# MCU.net
KiCad netlist of a schematic drawn in Altium Designer
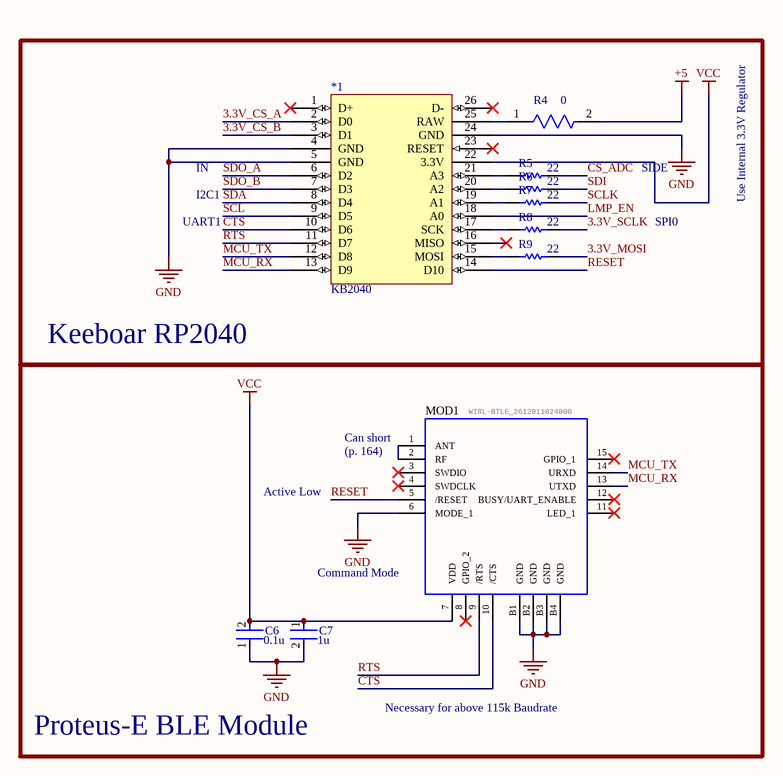
[diagram p0: MCU.SchDoc]

(export (version "E")
  (design (tool "Eeschema 10.0.6"))
  (components
    (comp (ref "*1")
      (value "KB2040")
      (footprint "CAC-254P3300X1775-26N")
      (description "Adafruit KB2040 - RP2040 Kee Boar Driver")
      (libsource (lib "UCLA") (part "KB2040-Symbol-1"))
    )
    (comp (ref "C6")
      (value "0.1u")
      (footprint "FP-GCJ188-0_2-IPC_C")
      (description "Cap Ceramic 0.1uF 50V X7R 10% Pad SMD 0603 Soft Termination +125°C Automotive T/R")
      (fields (field (name "TOLERANCE") "10%"))
      (libsource (lib "Altium Content Vault") (part "f23184f103b6ebe33a8c269c53dcba6"))
    )
    (comp (ref "C7")
      (value "1u")
      (footprint "FP-GCM188-0_1-IPC_B")
      (description "Ceramic Capacitor for Automotive 1uF  ±10% 16VDC X7R 0603 Paper T/R")
      (fields (field (name "VOLTAGE") "16V") (field (name "TOLERANCE") "10%"))
      (libsource (lib "Altium Content Vault") (part "02cd4be3c70576c341d710602a673aa"))
    )
    (comp (ref "MOD1")
      (value "WIRL-BTLE_2612011024000")
      (footprint "WE-FP-6")
      (description "Proteus-e Bluetooth® LE 5.1 Module")
      (fields (field (name "PART NUMBER") "2612011024000") (field (name "PUBLISHER") "Würth Elektronik"))
      (libsource (lib "WE_WIRL_Rev12") (part "WIRL-BTLE_2612011024000"))
    )
    (comp (ref "R4")
      (value "0")
      (footprint "FP-CRCW0603-MFG")
      (description "RES SMD 0 OHM JUMPER 1/10W 0603")
      (fields (field (name "TOLERANCE") "5%"))
      (libsource (lib "Altium Content Vault") (part "1029c3af85768c4190bb7ad29bc67b5"))
    )
    (comp (ref "R5")
      (value "22")
      (footprint "RESC1608X55X25LL10T15")
      (fields (field (name "MANUFACTURER") "Yageo") (field (name "PART NUMBER") "RC0603FR-1022RL"))
      (libsource (lib "Altium Content Vault") (part "RES"))
    )
    (comp (ref "R6")
      (value "22")
      (footprint "RESC1608X55X25LL10T15")
      (fields (field (name "MANUFACTURER") "Yageo") (field (name "PART NUMBER") "RC0603FR-1022RL"))
      (libsource (lib "Altium Content Vault") (part "RES"))
    )
    (comp (ref "R7")
      (value "22")
      (footprint "RESC1608X55X25LL10T15")
      (fields (field (name "MANUFACTURER") "Yageo") (field (name "PART NUMBER") "RC0603FR-1022RL"))
      (libsource (lib "Altium Content Vault") (part "RES"))
    )
    (comp (ref "R8")
      (value "22")
      (footprint "RESC1608X55X25LL10T15")
      (fields (field (name "MANUFACTURER") "Yageo") (field (name "PART NUMBER") "RC0603FR-1022RL"))
      (libsource (lib "Altium Content Vault") (part "RES"))
    )
    (comp (ref "R9")
      (value "22")
      (footprint "RESC1608X55X25LL10T15")
      (fields (field (name "MANUFACTURER") "Yageo") (field (name "PART NUMBER") "RC0603FR-1022RL"))
      (libsource (lib "Altium Content Vault") (part "RES"))
    )
  )
  (nets
    (net (code "1") (name "+5") (class "Default")
      (node (ref "R4") (pin "2") (pinfunction "2_2") (pintype "passive"))
    )
    (net (code "2") (name "/3.3V_CS_A") (class "Default")
      (node (ref "*1") (pin "2") (pinfunction "D0_2") (pintype "bidirectional"))
    )
    (net (code "3") (name "/3.3V_CS_B") (class "Default")
      (node (ref "*1") (pin "3") (pinfunction "D1_3") (pintype "bidirectional"))
    )
    (net (code "4") (name "/3.3V_MOSI") (class "Default")
      (node (ref "R9") (pin "2") (pinfunction "2_2") (pintype "passive"))
    )
    (net (code "5") (name "/3.3V_SCLK") (class "Default")
      (node (ref "R8") (pin "2") (pinfunction "2_2") (pintype "passive"))
    )
    (net (code "6") (name "/CS_ADC") (class "Default")
      (node (ref "R5") (pin "2") (pinfunction "2_2") (pintype "passive"))
    )
    (net (code "7") (name "/CTS") (class "Default")
      (node (ref "*1") (pin "10") (pinfunction "D6_10") (pintype "bidirectional"))
      (node (ref "MOD1") (pin "10") (pinfunction "/CTS_10") (pintype "passive"))
    )
    (net (code "8") (name "/LMP_EN") (class "Default")
      (node (ref "*1") (pin "18") (pinfunction "A0_18") (pintype "bidirectional"))
    )
    (net (code "9") (name "/MCU_RX") (class "Default")
      (node (ref "*1") (pin "13") (pinfunction "D9_13") (pintype "bidirectional"))
      (node (ref "MOD1") (pin "13") (pinfunction "UTXD_13") (pintype "passive"))
    )
    (net (code "10") (name "/MCU_TX") (class "Default")
      (node (ref "*1") (pin "12") (pinfunction "D8_12") (pintype "bidirectional"))
      (node (ref "MOD1") (pin "14") (pinfunction "URXD_14") (pintype "passive"))
    )
    (net (code "11") (name "/RESET") (class "Default")
      (node (ref "*1") (pin "14") (pinfunction "D10_14") (pintype "bidirectional"))
      (node (ref "MOD1") (pin "5") (pinfunction "/RESET_5") (pintype "passive"))
    )
    (net (code "12") (name "/RTS") (class "Default")
      (node (ref "*1") (pin "11") (pinfunction "D7_11") (pintype "bidirectional"))
      (node (ref "MOD1") (pin "9") (pinfunction "/RTS_9") (pintype "passive"))
    )
    (net (code "13") (name "/SCL") (class "Default")
      (node (ref "*1") (pin "9") (pinfunction "D5_9") (pintype "bidirectional"))
    )
    (net (code "14") (name "/SCLK") (class "Default")
      (node (ref "R7") (pin "2") (pinfunction "2_2") (pintype "passive"))
    )
    (net (code "15") (name "/SDA") (class "Default")
      (node (ref "*1") (pin "8") (pinfunction "D4_8") (pintype "bidirectional"))
    )
    (net (code "16") (name "/SDI") (class "Default")
      (node (ref "R6") (pin "2") (pinfunction "2_2") (pintype "passive"))
    )
    (net (code "17") (name "/SDO_A") (class "Default")
      (node (ref "*1") (pin "6") (pinfunction "D2_6") (pintype "bidirectional"))
    )
    (net (code "18") (name "/SDO_B") (class "Default")
      (node (ref "*1") (pin "7") (pinfunction "D3_7") (pintype "bidirectional"))
    )
    (net (code "19") (name "GND") (class "Default")
      (node (ref "*1") (pin "24") (pinfunction "GND_24") (pintype "power_in"))
      (node (ref "*1") (pin "4") (pinfunction "GND_4") (pintype "power_in"))
      (node (ref "*1") (pin "5") (pinfunction "GND_5") (pintype "power_in"))
      (node (ref "C6") (pin "1") (pinfunction "1_1") (pintype "passive"))
      (node (ref "C7") (pin "2") (pinfunction "2_2") (pintype "passive"))
      (node (ref "MOD1") (pin "6") (pinfunction "MODE_1_6") (pintype "passive"))
      (node (ref "MOD1") (pin "B1") (pinfunction "GND_B1") (pintype "passive"))
      (node (ref "MOD1") (pin "B2") (pinfunction "GND_B2") (pintype "passive"))
      (node (ref "MOD1") (pin "B3") (pinfunction "GND_B3") (pintype "passive"))
      (node (ref "MOD1") (pin "B4") (pinfunction "GND_B4") (pintype "passive"))
    )
    (net (code "20") (name "Net-(*1-A1)") (class "Default")
      (node (ref "*1") (pin "19") (pinfunction "A1_19") (pintype "bidirectional"))
      (node (ref "R7") (pin "1") (pinfunction "1_1") (pintype "passive"))
    )
    (net (code "21") (name "Net-(*1-A2)") (class "Default")
      (node (ref "*1") (pin "20") (pinfunction "A2_20") (pintype "bidirectional"))
      (node (ref "R6") (pin "1") (pinfunction "1_1") (pintype "passive"))
    )
    (net (code "22") (name "Net-(*1-A3)") (class "Default")
      (node (ref "*1") (pin "21") (pinfunction "A3_21") (pintype "bidirectional"))
      (node (ref "R5") (pin "1") (pinfunction "1_1") (pintype "passive"))
    )
    (net (code "23") (name "Net-(*1-MOSI)") (class "Default")
      (node (ref "*1") (pin "15") (pinfunction "MOSI_15") (pintype "bidirectional"))
      (node (ref "R9") (pin "1") (pinfunction "1_1") (pintype "passive"))
    )
    (net (code "24") (name "Net-(*1-RAW)") (class "Default")
      (node (ref "*1") (pin "25") (pinfunction "RAW_25") (pintype "power_in"))
      (node (ref "R4") (pin "1") (pinfunction "1_1") (pintype "passive"))
    )
    (net (code "25") (name "Net-(*1-SCK)") (class "Default")
      (node (ref "*1") (pin "17") (pinfunction "SCK_17") (pintype "bidirectional"))
      (node (ref "R8") (pin "1") (pinfunction "1_1") (pintype "passive"))
    )
    (net (code "26") (name "Net-(MOD1-ANT)") (class "Default")
      (node (ref "MOD1") (pin "1") (pinfunction "ANT_1") (pintype "passive"))
      (node (ref "MOD1") (pin "2") (pinfunction "RF_2") (pintype "passive"))
    )
    (net (code "27") (name "VCC") (class "Default")
      (node (ref "*1") (pin "22") (pinfunction "3.3V_22") (pintype "power_in"))
      (node (ref "C6") (pin "2") (pinfunction "2_2") (pintype "passive"))
      (node (ref "C7") (pin "1") (pinfunction "1_1") (pintype "passive"))
      (node (ref "MOD1") (pin "7") (pinfunction "VDD_7") (pintype "passive"))
    )
    (net (code "28") (name "unconnected-(*1-D+-Pad1)") (class "Default")
      (node (ref "*1") (pin "1") (pinfunction "D+_1") (pintype "bidirectional+no_connect"))
    )
    (net (code "29") (name "unconnected-(*1-D--Pad26)") (class "Default")
      (node (ref "*1") (pin "26") (pinfunction "D-_26") (pintype "bidirectional+no_connect"))
    )
    (net (code "30") (name "unconnected-(*1-MISO-Pad16)") (class "Default")
      (node (ref "*1") (pin "16") (pinfunction "MISO_16") (pintype "bidirectional+no_connect"))
    )
    (net (code "31") (name "unconnected-(*1-RESET-Pad23)") (class "Default")
      (node (ref "*1") (pin "23") (pinfunction "RESET_23") (pintype "input+no_connect"))
    )
    (net (code "32") (name "unconnected-(MOD1-BUSY{slash}UART_ENABLE-Pad12)") (class "Default")
      (node (ref "MOD1") (pin "12") (pinfunction "BUSY/UART_ENABLE_12") (pintype "passive+no_connect"))
    )
    (net (code "33") (name "unconnected-(MOD1-GPIO_1-Pad15)") (class "Default")
      (node (ref "MOD1") (pin "15") (pinfunction "GPIO_1_15") (pintype "passive+no_connect"))
    )
    (net (code "34") (name "unconnected-(MOD1-GPIO_2-Pad8)") (class "Default")
      (node (ref "MOD1") (pin "8") (pinfunction "GPIO_2_8") (pintype "passive+no_connect"))
    )
    (net (code "35") (name "unconnected-(MOD1-LED_1-Pad11)") (class "Default")
      (node (ref "MOD1") (pin "11") (pinfunction "LED_1_11") (pintype "passive+no_connect"))
    )
    (net (code "36") (name "unconnected-(MOD1-SWDCLK-Pad4)") (class "Default")
      (node (ref "MOD1") (pin "4") (pinfunction "SWDCLK_4") (pintype "passive+no_connect"))
    )
    (net (code "37") (name "unconnected-(MOD1-SWDIO-Pad3)") (class "Default")
      (node (ref "MOD1") (pin "3") (pinfunction "SWDIO_3") (pintype "passive+no_connect"))
    )
  )
)
